# ACIN.net
KiCad netlist of a schematic drawn in EAGLE
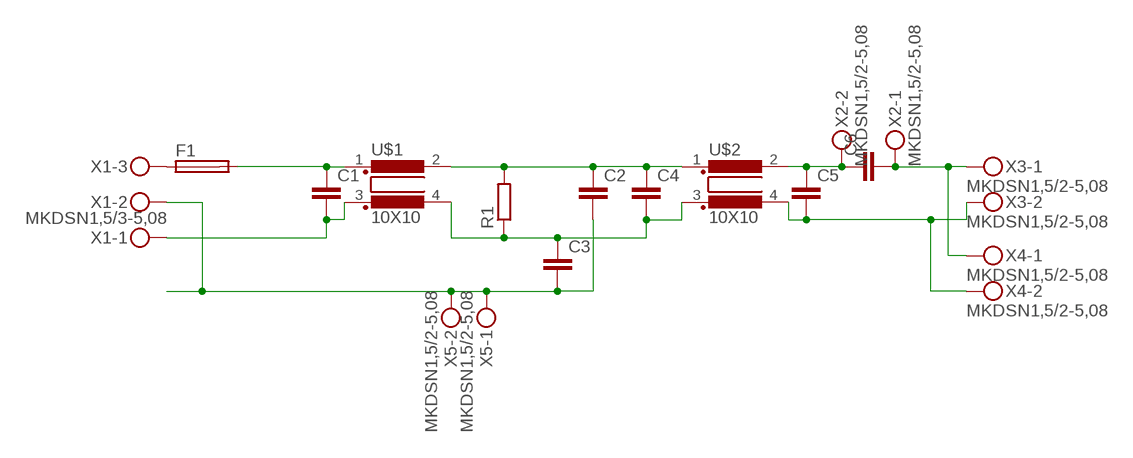
[diagram p0: schematic, sheet 1]

(export (version "E")
  (design (tool "Eeschema 10.0.6"))
  (components
    (comp (ref "C1")
      (value "C-EU225-087X268")
      (footprint "eagle-import:C225-087X268")
      (libsource (lib "eagle-import") (part "C-EU225-087X268"))
    )
    (comp (ref "C2")
      (value "C-EU102-054X133")
      (footprint "eagle-import:C102-054X133")
      (libsource (lib "eagle-import") (part "C-EU102-054X133"))
    )
    (comp (ref "C3")
      (value "C-EU102-054X133")
      (footprint "eagle-import:C102-054X133")
      (libsource (lib "eagle-import") (part "C-EU102-054X133"))
    )
    (comp (ref "C4")
      (value "C-EU225-087X268")
      (footprint "eagle-import:C225-087X268")
      (libsource (lib "eagle-import") (part "C-EU225-087X268"))
    )
    (comp (ref "C5")
      (value "C-EU225-087X268")
      (footprint "eagle-import:C225-087X268")
      (libsource (lib "eagle-import") (part "C-EU225-087X268"))
    )
    (comp (ref "C6")
      (value "C-EU075-042X103")
      (footprint "eagle-import:C075-042X103")
      (libsource (lib "eagle-import") (part "C-EU075-042X103"))
    )
    (comp (ref "F1")
      (value "SH22,5A")
      (footprint "eagle-import:SH22,5A")
      (fields (field (name "MPN") "0031.7701.11"))
      (libsource (lib "eagle-import") (part "SH22,5A"))
    )
    (comp (ref "R1")
      (value "R-EU_0309/12")
      (footprint "eagle-import:0309_12")
      (libsource (lib "eagle-import") (part "R-EU_0309/12"))
    )
    (comp (ref "U$1")
      (value "10X10")
      (footprint "eagle-import:10X10")
      (libsource (lib "eagle-import") (part "10X10"))
    )
    (comp (ref "U$2")
      (value "10X10")
      (footprint "eagle-import:10X10")
      (libsource (lib "eagle-import") (part "10X10"))
    )
    (comp (ref "X1")
      (value "MKDSN1,5/3-5,08")
      (footprint "eagle-import:MKDSN1,5_3-5,08")
      (libsource (lib "eagle-import") (part "MKDSN1,5/3-5,08"))
    )
    (comp (ref "X2")
      (value "MKDSN1,5/2-5,08")
      (footprint "eagle-import:MKDSN1,5_2-5,08")
      (libsource (lib "eagle-import") (part "MKDSN1,5/2-5,08"))
    )
    (comp (ref "X3")
      (value "MKDSN1,5/2-5,08")
      (footprint "eagle-import:MKDSN1,5_2-5,08")
      (libsource (lib "eagle-import") (part "MKDSN1,5/2-5,08"))
    )
    (comp (ref "X4")
      (value "MKDSN1,5/2-5,08")
      (footprint "eagle-import:MKDSN1,5_2-5,08")
      (libsource (lib "eagle-import") (part "MKDSN1,5/2-5,08"))
    )
    (comp (ref "X5")
      (value "MKDSN1,5/2-5,08")
      (footprint "eagle-import:MKDSN1,5_2-5,08")
      (libsource (lib "eagle-import") (part "MKDSN1,5/2-5,08"))
    )
  )
  (nets
    (net (code "1") (name "Net-(C1-Pad1)") (class "Default")
      (node (ref "C1") (pin "1") (pinfunction "1_1") (pintype "passive"))
      (node (ref "F1") (pin "2") (pinfunction "2_2") (pintype "passive"))
      (node (ref "U$1") (pin "1") (pinfunction "1_1") (pintype "passive"))
    )
    (net (code "2") (name "Net-(C2-Pad1)") (class "Default")
      (node (ref "C2") (pin "1") (pinfunction "1_1") (pintype "passive"))
      (node (ref "C4") (pin "1") (pinfunction "1_1") (pintype "passive"))
      (node (ref "R1") (pin "2") (pinfunction "2_2") (pintype "passive"))
      (node (ref "U$1") (pin "2") (pinfunction "2_2") (pintype "passive"))
      (node (ref "U$2") (pin "1") (pinfunction "1_1") (pintype "passive"))
    )
    (net (code "3") (name "Net-(C3-Pad1)") (class "Default")
      (node (ref "C3") (pin "1") (pinfunction "1_1") (pintype "passive"))
      (node (ref "C4") (pin "2") (pinfunction "2_2") (pintype "passive"))
      (node (ref "R1") (pin "1") (pinfunction "1_1") (pintype "passive"))
      (node (ref "U$1") (pin "4") (pinfunction "4_4") (pintype "passive"))
      (node (ref "U$2") (pin "3") (pinfunction "3_3") (pintype "passive"))
    )
    (net (code "4") (name "Net-(X1A-KL)") (class "Default")
      (node (ref "C1") (pin "2") (pinfunction "2_2") (pintype "passive"))
      (node (ref "U$1") (pin "3") (pinfunction "3_3") (pintype "passive"))
      (node (ref "X1") (pin "1") (pinfunction "KL_1") (pintype "passive"))
    )
    (net (code "5") (name "Net-(X1B-KL)") (class "Default")
      (node (ref "C2") (pin "2") (pinfunction "2_2") (pintype "passive"))
      (node (ref "C3") (pin "2") (pinfunction "2_2") (pintype "passive"))
      (node (ref "X1") (pin "2") (pinfunction "KL_2") (pintype "passive"))
      (node (ref "X5") (pin "1") (pinfunction "KL_1") (pintype "passive"))
      (node (ref "X5") (pin "2") (pinfunction "KL_2") (pintype "passive"))
    )
    (net (code "6") (name "Net-(X1C-KL)") (class "Default")
      (node (ref "F1") (pin "1") (pinfunction "1_1") (pintype "passive"))
      (node (ref "X1") (pin "3") (pinfunction "KL_3") (pintype "passive"))
    )
    (net (code "7") (name "Net-(X2A-KL)") (class "Default")
      (node (ref "C6") (pin "2") (pinfunction "2_2") (pintype "passive"))
      (node (ref "X2") (pin "1") (pinfunction "KL_1") (pintype "passive"))
      (node (ref "X3") (pin "1") (pinfunction "KL_1") (pintype "passive"))
      (node (ref "X4") (pin "1") (pinfunction "KL_1") (pintype "passive"))
    )
    (net (code "8") (name "Net-(X2B-KL)") (class "Default")
      (node (ref "C5") (pin "1") (pinfunction "1_1") (pintype "passive"))
      (node (ref "C6") (pin "1") (pinfunction "1_1") (pintype "passive"))
      (node (ref "U$2") (pin "2") (pinfunction "2_2") (pintype "passive"))
      (node (ref "X2") (pin "2") (pinfunction "KL_2") (pintype "passive"))
    )
    (net (code "9") (name "Net-(X3B-KL)") (class "Default")
      (node (ref "C5") (pin "2") (pinfunction "2_2") (pintype "passive"))
      (node (ref "U$2") (pin "4") (pinfunction "4_4") (pintype "passive"))
      (node (ref "X3") (pin "2") (pinfunction "KL_2") (pintype "passive"))
      (node (ref "X4") (pin "2") (pinfunction "KL_2") (pintype "passive"))
    )
  )
)
